# BW1097_SODIMM.net
KiCad netlist of a schematic drawn in Altium Designer
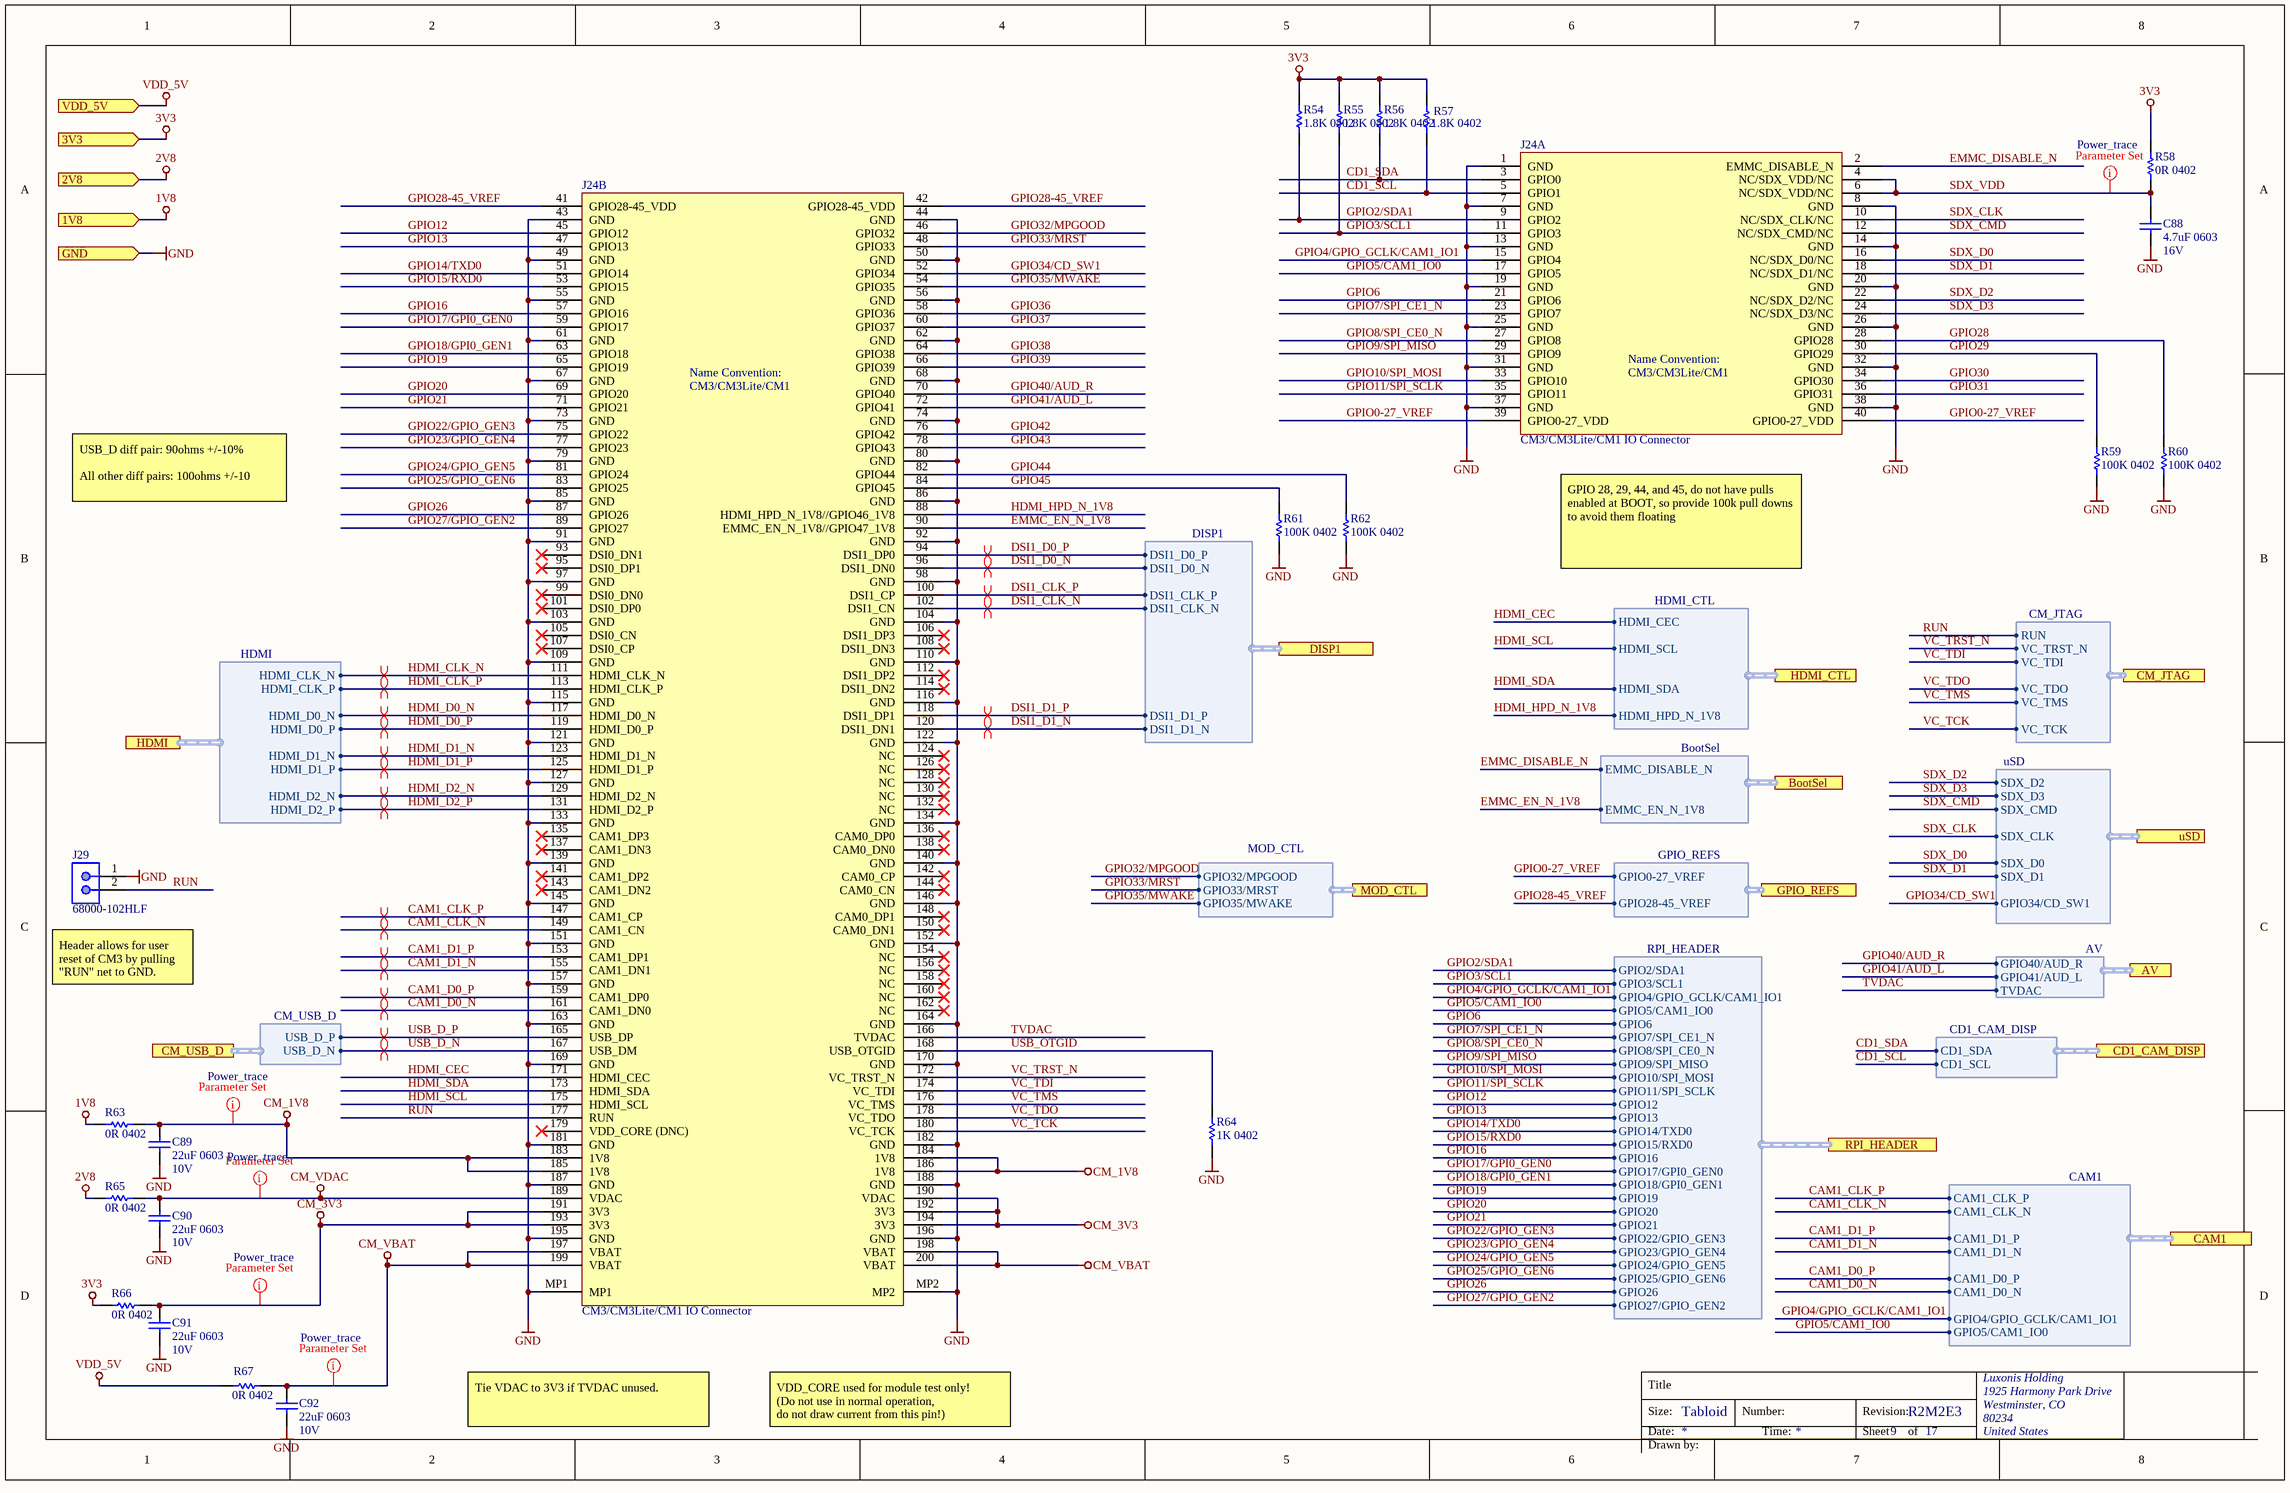
[diagram p0: BW1097_SODIMM.SchDoc]

(export (version "E")
  (design (tool "Eeschema 10.0.6"))
  (components
    (comp (ref "C88")
      (value "4.7uF 0603")
      (footprint "CAP_Altium_Vault_Generic:CAPC0603(1608)100_N")
      (description "CAP CER 4.7UF 16V X5R 0603 10%")
      (fields (field (name "TOLERANCE") "10%") (field (name "VOLTAGE RATING") "16V"))
      (libsource (lib "LuxonisMaster") (part "GRM188R61C475KAAJD"))
    )
    (comp (ref "C89")
      (value "22uF 0603")
      (footprint "CAP_Altium_Vault_Generic:CAPC0603(1608)100_N")
      (description "CAP CER 22UF 10V X5R 0603 20%")
      (fields (field (name "TOLERANCE") "20%") (field (name "VOLTAGE RATING") "10V"))
      (libsource (lib "LuxonisMaster") (part "GRM188R61A226ME15D"))
    )
    (comp (ref "C90")
      (value "22uF 0603")
      (footprint "CAP_Altium_Vault_Generic:CAPC0603(1608)100_N")
      (description "CAP CER 22UF 10V X5R 0603 20%")
      (fields (field (name "TOLERANCE") "20%") (field (name "VOLTAGE RATING") "10V"))
      (libsource (lib "LuxonisMaster") (part "GRM188R61A226ME15D"))
    )
    (comp (ref "C91")
      (value "22uF 0603")
      (footprint "CAP_Altium_Vault_Generic:CAPC0603(1608)100_N")
      (description "CAP CER 22UF 10V X5R 0603 20%")
      (fields (field (name "TOLERANCE") "20%") (field (name "VOLTAGE RATING") "10V"))
      (libsource (lib "LuxonisMaster") (part "GRM188R61A226ME15D"))
    )
    (comp (ref "C92")
      (value "22uF 0603")
      (footprint "CAP_Altium_Vault_Generic:CAPC0603(1608)100_N")
      (description "CAP CER 22UF 10V X5R 0603 20%")
      (fields (field (name "TOLERANCE") "20%") (field (name "VOLTAGE RATING") "10V"))
      (libsource (lib "LuxonisMaster") (part "GRM188R61A226ME15D"))
    )
    (comp (ref "J24")
      (value "CM3/CM3Lite/CM1 IO Connector")
      (footprint "LuxonisMaster:1473005-4")
      (description "CONN SKT SODIMM 200POS R/A SMD CM3/CM3Lite/CM1 IO Connector")
      (libsource (lib "LuxonisMaster") (part "1473005-4_ComputeModule"))
    )
    (comp (ref "J29")
      (value "68000-102HLF")
      (footprint "LuxonisMaster:68000-102HLF")
      (description "CONN HEADER VERT 2POS 2.54MM")
      (libsource (lib "LuxonisMaster") (part "68000-102HLF"))
    )
    (comp (ref "R54")
      (value "1.8K 0402")
      (footprint "RES_Altium_Vault_Generic:RESC0402(1005)_N")
      (description "RES SMD 1.8K OHM 1% 1/16W 0402")
      (fields (field (name "TOLERANCE") "1%"))
      (libsource (lib "LuxonisMaster") (part "RC0402FR-071K8L"))
    )
    (comp (ref "R55")
      (value "1.8K 0402")
      (footprint "RES_Altium_Vault_Generic:RESC0402(1005)_N")
      (description "RES SMD 1.8K OHM 1% 1/16W 0402")
      (fields (field (name "TOLERANCE") "1%"))
      (libsource (lib "LuxonisMaster") (part "RC0402FR-071K8L"))
    )
    (comp (ref "R56")
      (value "1.8K 0402")
      (footprint "RES_Altium_Vault_Generic:RESC0402(1005)_N")
      (description "RES SMD 1.8K OHM 1% 1/16W 0402")
      (fields (field (name "TOLERANCE") "1%"))
      (libsource (lib "LuxonisMaster") (part "RC0402FR-071K8L"))
    )
    (comp (ref "R57")
      (value "1.8K 0402")
      (footprint "RES_Altium_Vault_Generic:RESC0402(1005)_N")
      (description "RES SMD 1.8K OHM 1% 1/16W 0402")
      (fields (field (name "TOLERANCE") "1%"))
      (libsource (lib "LuxonisMaster") (part "RC0402FR-071K8L"))
    )
    (comp (ref "R58")
      (value "0R 0402")
      (footprint "RES_Altium_Vault_Generic:RESC0402(1005)_N")
      (description "RES SMD 0 OHM JUMPER 1/16W 0402")
      (fields (field (name "TOLERANCE") "5%"))
      (libsource (lib "LuxonisMaster") (part "CRCW04020000Z0ED"))
    )
    (comp (ref "R59")
      (value "100K 0402")
      (footprint "RES_Altium_Vault_Generic:RESC0402(1005)_N")
      (description "RES SMD 100K OHM 1% 1/16W 0402")
      (fields (field (name "TOLERANCE") "1%"))
      (libsource (lib "LuxonisMaster") (part "RC0402FR-07100KL"))
    )
    (comp (ref "R60")
      (value "100K 0402")
      (footprint "RES_Altium_Vault_Generic:RESC0402(1005)_N")
      (description "RES SMD 100K OHM 1% 1/16W 0402")
      (fields (field (name "TOLERANCE") "1%"))
      (libsource (lib "LuxonisMaster") (part "RC0402FR-07100KL"))
    )
    (comp (ref "R61")
      (value "100K 0402")
      (footprint "RES_Altium_Vault_Generic:RESC0402(1005)_N")
      (description "RES SMD 100K OHM 1% 1/16W 0402")
      (fields (field (name "TOLERANCE") "1%"))
      (libsource (lib "LuxonisMaster") (part "RC0402FR-07100KL"))
    )
    (comp (ref "R62")
      (value "100K 0402")
      (footprint "RES_Altium_Vault_Generic:RESC0402(1005)_N")
      (description "RES SMD 100K OHM 1% 1/16W 0402")
      (fields (field (name "TOLERANCE") "1%"))
      (libsource (lib "LuxonisMaster") (part "RC0402FR-07100KL"))
    )
    (comp (ref "R63")
      (value "0R 0402")
      (footprint "RES_Altium_Vault_Generic:RESC0402(1005)_N")
      (description "RES SMD 0 OHM JUMPER 1/16W 0402")
      (fields (field (name "TOLERANCE") "5%"))
      (libsource (lib "LuxonisMaster") (part "CRCW04020000Z0ED"))
    )
    (comp (ref "R64")
      (value "1K 0402")
      (footprint "RES_Altium_Vault_Generic:RESC0402(1005)_N")
      (fields (field (name "TOLERANCE") "1%"))
      (libsource (lib "LuxonisMaster") (part "RC0402FR-071KL"))
    )
    (comp (ref "R65")
      (value "0R 0402")
      (footprint "RES_Altium_Vault_Generic:RESC0402(1005)_N")
      (description "RES SMD 0 OHM JUMPER 1/16W 0402")
      (fields (field (name "TOLERANCE") "5%"))
      (libsource (lib "LuxonisMaster") (part "CRCW04020000Z0ED"))
    )
    (comp (ref "R66")
      (value "0R 0402")
      (footprint "RES_Altium_Vault_Generic:RESC0402(1005)_N")
      (description "RES SMD 0 OHM JUMPER 1/16W 0402")
      (fields (field (name "TOLERANCE") "5%"))
      (libsource (lib "LuxonisMaster") (part "CRCW04020000Z0ED"))
    )
    (comp (ref "R67")
      (value "0R 0402")
      (footprint "RES_Altium_Vault_Generic:RESC0402(1005)_N")
      (description "RES SMD 0 OHM JUMPER 1/16W 0402")
      (fields (field (name "TOLERANCE") "5%"))
      (libsource (lib "LuxonisMaster") (part "CRCW04020000Z0ED"))
    )
  )
  (nets
    (net (code "14") (name "/CAM1_CLK_N") (class "Default")
      (node (ref "J24") (pin "149") (pinfunction "CAM1_CN_149") (pintype "passive"))
    )
    (net (code "15") (name "/CAM1_CLK_P") (class "Default")
      (node (ref "J24") (pin "147") (pinfunction "CAM1_CP_147") (pintype "passive"))
    )
    (net (code "16") (name "/CAM1_D0_N") (class "Default")
      (node (ref "J24") (pin "161") (pinfunction "CAM1_DN0_161") (pintype "passive"))
    )
    (net (code "17") (name "/CAM1_D0_P") (class "Default")
      (node (ref "J24") (pin "159") (pinfunction "CAM1_DP0_159") (pintype "passive"))
    )
    (net (code "18") (name "/CAM1_D1_N") (class "Default")
      (node (ref "J24") (pin "155") (pinfunction "CAM1_DN1_155") (pintype "passive"))
    )
    (net (code "19") (name "/CAM1_D1_P") (class "Default")
      (node (ref "J24") (pin "153") (pinfunction "CAM1_DP1_153") (pintype "passive"))
    )
    (net (code "20") (name "/CD1_SCL") (class "Default")
      (node (ref "J24") (pin "5") (pinfunction "GPIO1_5") (pintype "passive"))
      (node (ref "R57") (pin "1") (pinfunction "1_1") (pintype "passive"))
    )
    (net (code "21") (name "/CD1_SDA") (class "Default")
      (node (ref "J24") (pin "3") (pinfunction "GPIO0_3") (pintype "passive"))
      (node (ref "R56") (pin "1") (pinfunction "1_1") (pintype "passive"))
    )
    (net (code "22") (name "/DSI1_CLK_N") (class "Default")
      (node (ref "J24") (pin "102") (pinfunction "DSI1_CN_102") (pintype "passive"))
    )
    (net (code "23") (name "/DSI1_CLK_P") (class "Default")
      (node (ref "J24") (pin "100") (pinfunction "DSI1_CP_100") (pintype "passive"))
    )
    (net (code "24") (name "/DSI1_D0_N") (class "Default")
      (node (ref "J24") (pin "96") (pinfunction "DSI1_DN0_96") (pintype "passive"))
    )
    (net (code "25") (name "/DSI1_D0_P") (class "Default")
      (node (ref "J24") (pin "94") (pinfunction "DSI1_DP0_94") (pintype "passive"))
    )
    (net (code "26") (name "/DSI1_D1_N") (class "Default")
      (node (ref "J24") (pin "120") (pinfunction "DSI1_DN1_120") (pintype "passive"))
    )
    (net (code "27") (name "/DSI1_D1_P") (class "Default")
      (node (ref "J24") (pin "118") (pinfunction "DSI1_DP1_118") (pintype "passive"))
    )
    (net (code "28") (name "/EMMC_DISABLE_N") (class "Default")
      (node (ref "J24") (pin "2") (pinfunction "EMMC_DISABLE_N_2") (pintype "passive"))
    )
    (net (code "29") (name "/EMMC_EN_N_1V8") (class "Default")
      (node (ref "J24") (pin "90") (pinfunction "EMMC_EN_N_1V8//GPIO47_1V8_90") (pintype "passive"))
    )
    (net (code "30") (name "/GPIO0-27_VREF") (class "Default")
      (node (ref "J24") (pin "39") (pinfunction "GPIO0-27_VDD_39") (pintype "passive"))
      (node (ref "J24") (pin "40") (pinfunction "GPIO0-27_VDD_40") (pintype "passive"))
    )
    (net (code "31") (name "/GPIO2{slash}SDA1") (class "Default")
      (node (ref "J24") (pin "9") (pinfunction "GPIO2_9") (pintype "passive"))
      (node (ref "R54") (pin "1") (pinfunction "1_1") (pintype "passive"))
    )
    (net (code "32") (name "/GPIO3{slash}SCL1") (class "Default")
      (node (ref "J24") (pin "11") (pinfunction "GPIO3_11") (pintype "passive"))
      (node (ref "R55") (pin "1") (pinfunction "1_1") (pintype "passive"))
    )
    (net (code "33") (name "/GPIO4{slash}GPIO_GCLK{slash}CAM1_IO1") (class "Default")
      (node (ref "J24") (pin "15") (pinfunction "GPIO4_15") (pintype "passive"))
    )
    (net (code "34") (name "/GPIO5{slash}CAM1_IO0") (class "Default")
      (node (ref "J24") (pin "17") (pinfunction "GPIO5_17") (pintype "passive"))
    )
    (net (code "35") (name "/GPIO6") (class "Default")
      (node (ref "J24") (pin "21") (pinfunction "GPIO6_21") (pintype "passive"))
    )
    (net (code "36") (name "/GPIO7{slash}SPI_CE1_N") (class "Default")
      (node (ref "J24") (pin "23") (pinfunction "GPIO7_23") (pintype "passive"))
    )
    (net (code "37") (name "/GPIO8{slash}SPI_CE0_N") (class "Default")
      (node (ref "J24") (pin "27") (pinfunction "GPIO8_27") (pintype "passive"))
    )
    (net (code "38") (name "/GPIO9{slash}SPI_MISO") (class "Default")
      (node (ref "J24") (pin "29") (pinfunction "GPIO9_29") (pintype "passive"))
    )
    (net (code "39") (name "/GPIO10{slash}SPI_MOSI") (class "Default")
      (node (ref "J24") (pin "33") (pinfunction "GPIO10_33") (pintype "passive"))
    )
    (net (code "40") (name "/GPIO11{slash}SPI_SCLK") (class "Default")
      (node (ref "J24") (pin "35") (pinfunction "GPIO11_35") (pintype "passive"))
    )
    (net (code "41") (name "/GPIO12") (class "Default")
      (node (ref "J24") (pin "45") (pinfunction "GPIO12_45") (pintype "passive"))
    )
    (net (code "42") (name "/GPIO13") (class "Default")
      (node (ref "J24") (pin "47") (pinfunction "GPIO13_47") (pintype "passive"))
    )
    (net (code "43") (name "/GPIO14{slash}TXD0") (class "Default")
      (node (ref "J24") (pin "51") (pinfunction "GPIO14_51") (pintype "passive"))
    )
    (net (code "44") (name "/GPIO15{slash}RXD0") (class "Default")
      (node (ref "J24") (pin "53") (pinfunction "GPIO15_53") (pintype "passive"))
    )
    (net (code "45") (name "/GPIO16") (class "Default")
      (node (ref "J24") (pin "57") (pinfunction "GPIO16_57") (pintype "passive"))
    )
    (net (code "46") (name "/GPIO17{slash}GPI0_GEN0") (class "Default")
      (node (ref "J24") (pin "59") (pinfunction "GPIO17_59") (pintype "passive"))
    )
    (net (code "47") (name "/GPIO18{slash}GPI0_GEN1") (class "Default")
      (node (ref "J24") (pin "63") (pinfunction "GPIO18_63") (pintype "passive"))
    )
    (net (code "48") (name "/GPIO19") (class "Default")
      (node (ref "J24") (pin "65") (pinfunction "GPIO19_65") (pintype "passive"))
    )
    (net (code "49") (name "/GPIO20") (class "Default")
      (node (ref "J24") (pin "69") (pinfunction "GPIO20_69") (pintype "passive"))
    )
    (net (code "50") (name "/GPIO21") (class "Default")
      (node (ref "J24") (pin "71") (pinfunction "GPIO21_71") (pintype "passive"))
    )
    (net (code "51") (name "/GPIO22{slash}GPIO_GEN3") (class "Default")
      (node (ref "J24") (pin "75") (pinfunction "GPIO22_75") (pintype "passive"))
    )
    (net (code "52") (name "/GPIO23{slash}GPIO_GEN4") (class "Default")
      (node (ref "J24") (pin "77") (pinfunction "GPIO23_77") (pintype "passive"))
    )
    (net (code "53") (name "/GPIO24{slash}GPIO_GEN5") (class "Default")
      (node (ref "J24") (pin "81") (pinfunction "GPIO24_81") (pintype "passive"))
    )
    (net (code "54") (name "/GPIO25{slash}GPIO_GEN6") (class "Default")
      (node (ref "J24") (pin "83") (pinfunction "GPIO25_83") (pintype "passive"))
    )
    (net (code "55") (name "/GPIO26") (class "Default")
      (node (ref "J24") (pin "87") (pinfunction "GPIO26_87") (pintype "passive"))
    )
    (net (code "56") (name "/GPIO27{slash}GPIO_GEN2") (class "Default")
      (node (ref "J24") (pin "89") (pinfunction "GPIO27_89") (pintype "passive"))
    )
    (net (code "57") (name "/GPIO28") (class "Default")
      (node (ref "J24") (pin "28") (pinfunction "GPIO28_28") (pintype "passive"))
      (node (ref "R60") (pin "2") (pinfunction "2_2") (pintype "passive"))
    )
    (net (code "58") (name "/GPIO28-45_VREF") (class "Default")
      (node (ref "J24") (pin "41") (pinfunction "GPIO28-45_VDD_41") (pintype "passive"))
      (node (ref "J24") (pin "42") (pinfunction "GPIO28-45_VDD_42") (pintype "passive"))
    )
    (net (code "59") (name "/GPIO29") (class "Default")
      (node (ref "J24") (pin "30") (pinfunction "GPIO29_30") (pintype "passive"))
      (node (ref "R59") (pin "2") (pinfunction "2_2") (pintype "passive"))
    )
    (net (code "60") (name "/GPIO30") (class "Default")
      (node (ref "J24") (pin "34") (pinfunction "GPIO30_34") (pintype "passive"))
    )
    (net (code "61") (name "/GPIO31") (class "Default")
      (node (ref "J24") (pin "36") (pinfunction "GPIO31_36") (pintype "passive"))
    )
    (net (code "62") (name "/GPIO32{slash}MPGOOD") (class "Default")
      (node (ref "J24") (pin "46") (pinfunction "GPIO32_46") (pintype "passive"))
    )
    (net (code "63") (name "/GPIO33{slash}MRST") (class "Default")
      (node (ref "J24") (pin "48") (pinfunction "GPIO33_48") (pintype "passive"))
    )
    (net (code "64") (name "/GPIO34{slash}CD_SW1") (class "Default")
      (node (ref "J24") (pin "52") (pinfunction "GPIO34_52") (pintype "passive"))
    )
    (net (code "65") (name "/GPIO35{slash}MWAKE") (class "Default")
      (node (ref "J24") (pin "54") (pinfunction "GPIO35_54") (pintype "passive"))
    )
    (net (code "66") (name "/GPIO36") (class "Default")
      (node (ref "J24") (pin "58") (pinfunction "GPIO36_58") (pintype "passive"))
    )
    (net (code "67") (name "/GPIO37") (class "Default")
      (node (ref "J24") (pin "60") (pinfunction "GPIO37_60") (pintype "passive"))
    )
    (net (code "68") (name "/GPIO38") (class "Default")
      (node (ref "J24") (pin "64") (pinfunction "GPIO38_64") (pintype "passive"))
    )
    (net (code "69") (name "/GPIO39") (class "Default")
      (node (ref "J24") (pin "66") (pinfunction "GPIO39_66") (pintype "passive"))
    )
    (net (code "70") (name "/GPIO40{slash}AUD_R") (class "Default")
      (node (ref "J24") (pin "70") (pinfunction "GPIO40_70") (pintype "passive"))
    )
    (net (code "71") (name "/GPIO41{slash}AUD_L") (class "Default")
      (node (ref "J24") (pin "72") (pinfunction "GPIO41_72") (pintype "passive"))
    )
    (net (code "72") (name "/GPIO42") (class "Default")
      (node (ref "J24") (pin "76") (pinfunction "GPIO42_76") (pintype "passive"))
    )
    (net (code "73") (name "/GPIO43") (class "Default")
      (node (ref "J24") (pin "78") (pinfunction "GPIO43_78") (pintype "passive"))
    )
    (net (code "74") (name "/GPIO44") (class "Default")
      (node (ref "J24") (pin "82") (pinfunction "GPIO44_82") (pintype "passive"))
      (node (ref "R62") (pin "2") (pinfunction "2_2") (pintype "passive"))
    )
    (net (code "75") (name "/GPIO45") (class "Default")
      (node (ref "J24") (pin "84") (pinfunction "GPIO45_84") (pintype "passive"))
      (node (ref "R61") (pin "2") (pinfunction "2_2") (pintype "passive"))
    )
    (net (code "76") (name "/HDMI_CEC") (class "Default")
      (node (ref "J24") (pin "171") (pinfunction "HDMI_CEC_171") (pintype "passive"))
    )
    (net (code "77") (name "/HDMI_CLK_N") (class "Default")
      (node (ref "J24") (pin "111") (pinfunction "HDMI_CLK_N_111") (pintype "passive"))
    )
    (net (code "78") (name "/HDMI_CLK_P") (class "Default")
      (node (ref "J24") (pin "113") (pinfunction "HDMI_CLK_P_113") (pintype "passive"))
    )
    (net (code "79") (name "/HDMI_D0_N") (class "Default")
      (node (ref "J24") (pin "117") (pinfunction "HDMI_D0_N_117") (pintype "passive"))
    )
    (net (code "80") (name "/HDMI_D0_P") (class "Default")
      (node (ref "J24") (pin "119") (pinfunction "HDMI_D0_P_119") (pintype "passive"))
    )
    (net (code "81") (name "/HDMI_D1_N") (class "Default")
      (node (ref "J24") (pin "123") (pinfunction "HDMI_D1_N_123") (pintype "passive"))
    )
    (net (code "82") (name "/HDMI_D1_P") (class "Default")
      (node (ref "J24") (pin "125") (pinfunction "HDMI_D1_P_125") (pintype "passive"))
    )
    (net (code "83") (name "/HDMI_D2_N") (class "Default")
      (node (ref "J24") (pin "129") (pinfunction "HDMI_D2_N_129") (pintype "passive"))
    )
    (net (code "84") (name "/HDMI_D2_P") (class "Default")
      (node (ref "J24") (pin "131") (pinfunction "HDMI_D2_P_131") (pintype "passive"))
    )
    (net (code "85") (name "/HDMI_HPD_N_1V8") (class "Default")
      (node (ref "J24") (pin "88") (pinfunction "HDMI_HPD_N_1V8//GPIO46_1V8_88") (pintype "passive"))
    )
    (net (code "86") (name "/HDMI_SCL") (class "Default")
      (node (ref "J24") (pin "175") (pinfunction "HDMI_SCL_175") (pintype "passive"))
    )
    (net (code "87") (name "/HDMI_SDA") (class "Default")
      (node (ref "J24") (pin "173") (pinfunction "HDMI_SDA_173") (pintype "passive"))
    )
    (net (code "88") (name "/RUN") (class "Default")
      (node (ref "J24") (pin "177") (pinfunction "RUN_177") (pintype "passive"))
      (node (ref "J29") (pin "2") (pinfunction "2_2") (pintype "passive"))
    )
    (net (code "89") (name "/SDX_CLK") (class "Default")
      (node (ref "J24") (pin "10") (pinfunction "NC/SDX_CLK/NC_10") (pintype "passive"))
    )
    (net (code "90") (name "/SDX_CMD") (class "Default")
      (node (ref "J24") (pin "12") (pinfunction "NC/SDX_CMD/NC_12") (pintype "passive"))
    )
    (net (code "91") (name "/SDX_D0") (class "Default")
      (node (ref "J24") (pin "16") (pinfunction "NC/SDX_D0/NC_16") (pintype "passive"))
    )
    (net (code "92") (name "/SDX_D1") (class "Default")
      (node (ref "J24") (pin "18") (pinfunction "NC/SDX_D1/NC_18") (pintype "passive"))
    )
    (net (code "93") (name "/SDX_D2") (class "Default")
      (node (ref "J24") (pin "22") (pinfunction "NC/SDX_D2/NC_22") (pintype "passive"))
    )
    (net (code "94") (name "/SDX_D3") (class "Default")
      (node (ref "J24") (pin "24") (pinfunction "NC/SDX_D3/NC_24") (pintype "passive"))
    )
    (net (code "95") (name "/SDX_VDD") (class "Default")
      (node (ref "C88") (pin "2") (pinfunction "2_2") (pintype "passive"))
      (node (ref "J24") (pin "4") (pinfunction "NC/SDX_VDD/NC_4") (pintype "passive"))
      (node (ref "J24") (pin "6") (pinfunction "NC/SDX_VDD/NC_6") (pintype "passive"))
      (node (ref "R58") (pin "1") (pinfunction "1_1") (pintype "passive"))
    )
    (net (code "96") (name "/TVDAC") (class "Default")
      (node (ref "J24") (pin "166") (pinfunction "TVDAC_166") (pintype "passive"))
    )
    (net (code "97") (name "/USB_D_N") (class "Default")
      (node (ref "J24") (pin "167") (pinfunction "USB_DM_167") (pintype "passive"))
    )
    (net (code "98") (name "/USB_D_P") (class "Default")
      (node (ref "J24") (pin "165") (pinfunction "USB_DP_165") (pintype "passive"))
    )
    (net (code "99") (name "/USB_OTGID") (class "Default")
      (node (ref "J24") (pin "168") (pinfunction "USB_OTGID_168") (pintype "passive"))
      (node (ref "R64") (pin "2") (pinfunction "2_2") (pintype "passive"))
    )
    (net (code "100") (name "/VC_TCK") (class "Default")
      (node (ref "J24") (pin "180") (pinfunction "VC_TCK_180") (pintype "passive"))
    )
    (net (code "101") (name "/VC_TDI") (class "Default")
      (node (ref "J24") (pin "174") (pinfunction "VC_TDI_174") (pintype "passive"))
    )
    (net (code "102") (name "/VC_TDO") (class "Default")
      (node (ref "J24") (pin "178") (pinfunction "VC_TDO_178") (pintype "passive"))
    )
    (net (code "103") (name "/VC_TMS") (class "Default")
      (node (ref "J24") (pin "176") (pinfunction "VC_TMS_176") (pintype "passive"))
    )
    (net (code "104") (name "/VC_TRST_N") (class "Default")
      (node (ref "J24") (pin "172") (pinfunction "VC_TRST_N_172") (pintype "passive"))
    )
    (net (code "118") (name "1V8") (class "Default")
      (node (ref "R63") (pin "1") (pinfunction "1_1") (pintype "passive"))
    )
    (net (code "119") (name "2V8") (class "Default")
      (node (ref "R65") (pin "1") (pinfunction "1_1") (pintype "passive"))
    )
    (net (code "120") (name "3V3") (class "Default")
      (node (ref "R54") (pin "2") (pinfunction "2_2") (pintype "passive"))
      (node (ref "R55") (pin "2") (pinfunction "2_2") (pintype "passive"))
      (node (ref "R56") (pin "2") (pinfunction "2_2") (pintype "passive"))
      (node (ref "R57") (pin "2") (pinfunction "2_2") (pintype "passive"))
      (node (ref "R58") (pin "2") (pinfunction "2_2") (pintype "passive"))
      (node (ref "R66") (pin "1") (pinfunction "1_1") (pintype "passive"))
    )
    (net (code "121") (name "CM_1V8") (class "Default")
      (node (ref "C89") (pin "1") (pinfunction "1_1") (pintype "passive"))
      (node (ref "J24") (pin "183") (pinfunction "1V8_183") (pintype "passive"))
      (node (ref "J24") (pin "184") (pinfunction "1V8_184") (pintype "passive"))
      (node (ref "J24") (pin "185") (pinfunction "1V8_185") (pintype "passive"))
      (node (ref "J24") (pin "186") (pinfunction "1V8_186") (pintype "passive"))
      (node (ref "R63") (pin "2") (pinfunction "2_2") (pintype "passive"))
    )
    (net (code "122") (name "CM_3V3") (class "Default")
      (node (ref "C91") (pin "1") (pinfunction "1_1") (pintype "passive"))
      (node (ref "J24") (pin "190") (pinfunction "VDAC_190") (pintype "passive"))
      (node (ref "J24") (pin "191") (pinfunction "3V3_191") (pintype "passive"))
      (node (ref "J24") (pin "192") (pinfunction "3V3_192") (pintype "passive"))
      (node (ref "J24") (pin "193") (pinfunction "3V3_193") (pintype "passive"))
      (node (ref "J24") (pin "194") (pinfunction "3V3_194") (pintype "passive"))
      (node (ref "R66") (pin "2") (pinfunction "2_2") (pintype "passive"))
    )
    (net (code "123") (name "CM_VBAT") (class "Default")
      (node (ref "C92") (pin "1") (pinfunction "1_1") (pintype "passive"))
      (node (ref "J24") (pin "197") (pinfunction "VBAT_197") (pintype "passive"))
      (node (ref "J24") (pin "198") (pinfunction "VBAT_198") (pintype "passive"))
      (node (ref "J24") (pin "199") (pinfunction "VBAT_199") (pintype "passive"))
      (node (ref "J24") (pin "200") (pinfunction "VBAT_200") (pintype "passive"))
      (node (ref "R67") (pin "2") (pinfunction "2_2") (pintype "passive"))
    )
    (net (code "124") (name "CM_VDAC") (class "Default")
      (node (ref "C90") (pin "1") (pinfunction "1_1") (pintype "passive"))
      (node (ref "J24") (pin "189") (pinfunction "VDAC_189") (pintype "passive"))
      (node (ref "R65") (pin "2") (pinfunction "2_2") (pintype "passive"))
    )
    (net (code "125") (name "GND") (class "Default")
      (node (ref "C88") (pin "1") (pinfunction "1_1") (pintype "passive"))
      (node (ref "C89") (pin "2") (pinfunction "2_2") (pintype "passive"))
      (node (ref "C90") (pin "2") (pinfunction "2_2") (pintype "passive"))
      (node (ref "C91") (pin "2") (pinfunction "2_2") (pintype "passive"))
      (node (ref "C92") (pin "2") (pinfunction "2_2") (pintype "passive"))
      (node (ref "J24") (pin "1") (pinfunction "GND_1") (pintype "passive"))
      (node (ref "J24") (pin "103") (pinfunction "GND_103") (pintype "passive"))
      (node (ref "J24") (pin "104") (pinfunction "GND_104") (pintype "passive"))
      (node (ref "J24") (pin "109") (pinfunction "GND_109") (pintype "passive"))
      (node (ref "J24") (pin "110") (pinfunction "GND_110") (pintype "passive"))
      (node (ref "J24") (pin "115") (pinfunction "GND_115") (pintype "passive"))
      (node (ref "J24") (pin "116") (pinfunction "GND_116") (pintype "passive"))
      (node (ref "J24") (pin "121") (pinfunction "GND_121") (pintype "passive"))
      (node (ref "J24") (pin "122") (pinfunction "GND_122") (pintype "passive"))
      (node (ref "J24") (pin "127") (pinfunction "GND_127") (pintype "passive"))
      (node (ref "J24") (pin "13") (pinfunction "GND_13") (pintype "passive"))
      (node (ref "J24") (pin "133") (pinfunction "GND_133") (pintype "passive"))
      (node (ref "J24") (pin "134") (pinfunction "GND_134") (pintype "passive"))
      (node (ref "J24") (pin "139") (pinfunction "GND_139") (pintype "passive"))
      (node (ref "J24") (pin "14") (pinfunction "GND_14") (pintype "passive"))
      (node (ref "J24") (pin "140") (pinfunction "GND_140") (pintype "passive"))
      (node (ref "J24") (pin "145") (pinfunction "GND_145") (pintype "passive"))
      (node (ref "J24") (pin "146") (pinfunction "GND_146") (pintype "passive"))
      (node (ref "J24") (pin "151") (pinfunction "GND_151") (pintype "passive"))
      (node (ref "J24") (pin "152") (pinfunction "GND_152") (pintype "passive"))
      (node (ref "J24") (pin "157") (pinfunction "GND_157") (pintype "passive"))
      (node (ref "J24") (pin "163") (pinfunction "GND_163") (pintype "passive"))
      (node (ref "J24") (pin "164") (pinfunction "GND_164") (pintype "passive"))
      (node (ref "J24") (pin "169") (pinfunction "GND_169") (pintype "passive"))
      (node (ref "J24") (pin "170") (pinfunction "GND_170") (pintype "passive"))
      (node (ref "J24") (pin "181") (pinfunction "GND_181") (pintype "passive"))
      (node (ref "J24") (pin "182") (pinfunction "GND_182") (pintype "passive"))
      (node (ref "J24") (pin "187") (pinfunction "GND_187") (pintype "passive"))
      (node (ref "J24") (pin "188") (pinfunction "GND_188") (pintype "passive"))
      (node (ref "J24") (pin "19") (pinfunction "GND_19") (pintype "passive"))
      (node (ref "J24") (pin "195") (pinfunction "GND_195") (pintype "passive"))
      (node (ref "J24") (pin "196") (pinfunction "GND_196") (pintype "passive"))
      (node (ref "J24") (pin "20") (pinfunction "GND_20") (pintype "passive"))
      (node (ref "J24") (pin "25") (pinfunction "GND_25") (pintype "passive"))
      (node (ref "J24") (pin "26") (pinfunction "GND_26") (pintype "passive"))
      (node (ref "J24") (pin "31") (pinfunction "GND_31") (pintype "passive"))
      (node (ref "J24") (pin "32") (pinfunction "GND_32") (pintype "passive"))
      (node (ref "J24") (pin "37") (pinfunction "GND_37") (pintype "passive"))
      (node (ref "J24") (pin "38") (pinfunction "GND_38") (pintype "passive"))
      (node (ref "J24") (pin "43") (pinfunction "GND_43") (pintype "passive"))
      (node (ref "J24") (pin "44") (pinfunction "GND_44") (pintype "passive"))
      (node (ref "J24") (pin "49") (pinfunction "GND_49") (pintype "passive"))
      (node (ref "J24") (pin "50") (pinfunction "GND_50") (pintype "passive"))
      (node (ref "J24") (pin "55") (pinfunction "GND_55") (pintype "passive"))
      (node (ref "J24") (pin "56") (pinfunction "GND_56") (pintype "passive"))
      (node (ref "J24") (pin "61") (pinfunction "GND_61") (pintype "passive"))
      (node (ref "J24") (pin "62") (pinfunction "GND_62") (pintype "passive"))
      (node (ref "J24") (pin "67") (pinfunction "GND_67") (pintype "passive"))
      (node (ref "J24") (pin "68") (pinfunction "GND_68") (pintype "passive"))
      (node (ref "J24") (pin "7") (pinfunction "GND_7") (pintype "passive"))
      (node (ref "J24") (pin "73") (pinfunction "GND_73") (pintype "passive"))
      (node (ref "J24") (pin "74") (pinfunction "GND_74") (pintype "passive"))
      (node (ref "J24") (pin "79") (pinfunction "GND_79") (pintype "passive"))
      (node (ref "J24") (pin "8") (pinfunction "GND_8") (pintype "passive"))
      (node (ref "J24") (pin "80") (pinfunction "GND_80") (pintype "passive"))
      (node (ref "J24") (pin "85") (pinfunction "GND_85") (pintype "passive"))
      (node (ref "J24") (pin "86") (pinfunction "GND_86") (pintype "passive"))
      (node (ref "J24") (pin "91") (pinfunction "GND_91") (pintype "passive"))
      (node (ref "J24") (pin "92") (pinfunction "GND_92") (pintype "passive"))
      (node (ref "J24") (pin "97") (pinfunction "GND_97") (pintype "passive"))
      (node (ref "J24") (pin "98") (pinfunction "GND_98") (pintype "passive"))
      (node (ref "J24") (pin "MP1") (pinfunction "MP1_MP1") (pintype "passive"))
      (node (ref "J24") (pin "MP2") (pinfunction "MP2_MP2") (pintype "passive"))
      (node (ref "J29") (pin "1") (pinfunction "1_1") (pintype "passive"))
      (node (ref "R59") (pin "1") (pinfunction "1_1") (pintype "passive"))
      (node (ref "R60") (pin "1") (pinfunction "1_1") (pintype "passive"))
      (node (ref "R61") (pin "1") (pinfunction "1_1") (pintype "passive"))
      (node (ref "R62") (pin "1") (pinfunction "1_1") (pintype "passive"))
      (node (ref "R64") (pin "1") (pinfunction "1_1") (pintype "passive"))
    )
    (net (code "126") (name "VDD_5V") (class "Default")
      (node (ref "R67") (pin "1") (pinfunction "1_1") (pintype "passive"))
    )
    (net (code "127") (name "unconnected-(J24B-CAM0_CN-Pad144)") (class "Default")
      (node (ref "J24") (pin "144") (pinfunction "CAM0_CN_144") (pintype "passive+no_connect"))
    )
    (net (code "128") (name "unconnected-(J24B-CAM0_CP-Pad142)") (class "Default")
      (node (ref "J24") (pin "142") (pinfunction "CAM0_CP_142") (pintype "passive+no_connect"))
    )
    (net (code "129") (name "unconnected-(J24B-CAM0_DN0-Pad138)") (class "Default")
      (node (ref "J24") (pin "138") (pinfunction "CAM0_DN0_138") (pintype "passive+no_connect"))
    )
    (net (code "130") (name "unconnected-(J24B-CAM0_DN1-Pad150)") (class "Default")
      (node (ref "J24") (pin "150") (pinfunction "CAM0_DN1_150") (pintype "passive+no_connect"))
    )
    (net (code "131") (name "unconnected-(J24B-CAM0_DP0-Pad136)") (class "Default")
      (node (ref "J24") (pin "136") (pinfunction "CAM0_DP0_136") (pintype "passive+no_connect"))
    )
    (net (code "132") (name "unconnected-(J24B-CAM0_DP1-Pad148)") (class "Default")
      (node (ref "J24") (pin "148") (pinfunction "CAM0_DP1_148") (pintype "passive+no_connect"))
    )
    (net (code "133") (name "unconnected-(J24B-CAM1_DN2-Pad143)") (class "Default")
      (node (ref "J24") (pin "143") (pinfunction "CAM1_DN2_143") (pintype "passive+no_connect"))
    )
    (net (code "134") (name "unconnected-(J24B-CAM1_DN3-Pad137)") (class "Default")
      (node (ref "J24") (pin "137") (pinfunction "CAM1_DN3_137") (pintype "passive+no_connect"))
    )
    (net (code "135") (name "unconnected-(J24B-CAM1_DP2-Pad141)") (class "Default")
      (node (ref "J24") (pin "141") (pinfunction "CAM1_DP2_141") (pintype "passive+no_connect"))
    )
    (net (code "136") (name "unconnected-(J24B-CAM1_DP3-Pad135)") (class "Default")
      (node (ref "J24") (pin "135") (pinfunction "CAM1_DP3_135") (pintype "passive+no_connect"))
    )
    (net (code "137") (name "unconnected-(J24B-DSI0_CN-Pad105)") (class "Default")
      (node (ref "J24") (pin "105") (pinfunction "DSI0_CN_105") (pintype "passive+no_connect"))
    )
    (net (code "138") (name "unconnected-(J24B-DSI0_CP-Pad107)") (class "Default")
      (node (ref "J24") (pin "107") (pinfunction "DSI0_CP_107") (pintype "passive+no_connect"))
    )
    (net (code "139") (name "unconnected-(J24B-DSI0_DN0-Pad99)") (class "Default")
      (node (ref "J24") (pin "99") (pinfunction "DSI0_DN0_99") (pintype "passive+no_connect"))
    )
    (net (code "140") (name "unconnected-(J24B-DSI0_DN1-Pad93)") (class "Default")
      (node (ref "J24") (pin "93") (pinfunction "DSI0_DN1_93") (pintype "passive+no_connect"))
    )
    (net (code "141") (name "unconnected-(J24B-DSI0_DP0-Pad101)") (class "Default")
      (node (ref "J24") (pin "101") (pinfunction "DSI0_DP0_101") (pintype "passive+no_connect"))
    )
    (net (code "142") (name "unconnected-(J24B-DSI0_DP1-Pad95)") (class "Default")
      (node (ref "J24") (pin "95") (pinfunction "DSI0_DP1_95") (pintype "passive+no_connect"))
    )
    (net (code "143") (name "unconnected-(J24B-DSI1_DN2-Pad114)") (class "Default")
      (node (ref "J24") (pin "114") (pinfunction "DSI1_DN2_114") (pintype "passive+no_connect"))
    )
    (net (code "144") (name "unconnected-(J24B-DSI1_DN3-Pad108)") (class "Default")
      (node (ref "J24") (pin "108") (pinfunction "DSI1_DN3_108") (pintype "passive+no_connect"))
    )
    (net (code "145") (name "unconnected-(J24B-DSI1_DP2-Pad112)") (class "Default")
      (node (ref "J24") (pin "112") (pinfunction "DSI1_DP2_112") (pintype "passive+no_connect"))
    )
    (net (code "146") (name "unconnected-(J24B-DSI1_DP3-Pad106)") (class "Default")
      (node (ref "J24") (pin "106") (pinfunction "DSI1_DP3_106") (pintype "passive+no_connect"))
    )
    (net (code "147") (name "unconnected-(J24B-NC-Pad124)") (class "Default")
      (node (ref "J24") (pin "124") (pinfunction "NC_124") (pintype "passive+no_connect"))
    )
    (net (code "148") (name "unconnected-(J24B-NC-Pad126)") (class "Default")
      (node (ref "J24") (pin "126") (pinfunction "NC_126") (pintype "passive+no_connect"))
    )
    (net (code "149") (name "unconnected-(J24B-NC-Pad128)") (class "Default")
      (node (ref "J24") (pin "128") (pinfunction "NC_128") (pintype "passive+no_connect"))
    )
    (net (code "150") (name "unconnected-(J24B-NC-Pad130)") (class "Default")
      (node (ref "J24") (pin "130") (pinfunction "NC_130") (pintype "passive+no_connect"))
    )
    (net (code "151") (name "unconnected-(J24B-NC-Pad132)") (class "Default")
      (node (ref "J24") (pin "132") (pinfunction "NC_132") (pintype "passive+no_connect"))
    )
    (net (code "152") (name "unconnected-(J24B-NC-Pad154)") (class "Default")
      (node (ref "J24") (pin "154") (pinfunction "NC_154") (pintype "passive+no_connect"))
    )
    (net (code "153") (name "unconnected-(J24B-NC-Pad156)") (class "Default")
      (node (ref "J24") (pin "156") (pinfunction "NC_156") (pintype "passive+no_connect"))
    )
    (net (code "154") (name "unconnected-(J24B-NC-Pad158)") (class "Default")
      (node (ref "J24") (pin "158") (pinfunction "NC_158") (pintype "passive+no_connect"))
    )
    (net (code "155") (name "unconnected-(J24B-NC-Pad160)") (class "Default")
      (node (ref "J24") (pin "160") (pinfunction "NC_160") (pintype "passive+no_connect"))
    )
    (net (code "156") (name "unconnected-(J24B-NC-Pad162)") (class "Default")
      (node (ref "J24") (pin "162") (pinfunction "NC_162") (pintype "passive+no_connect"))
    )
    (net (code "157") (name "unconnected-(J24B-VDD_CORE_(DNC)-Pad179)") (class "Default")
      (node (ref "J24") (pin "179") (pinfunction "VDD_CORE_(DNC)_179") (pintype "passive+no_connect"))
    )
  )
)
